# Power.net
KiCad netlist of a schematic drawn in Altium Designer
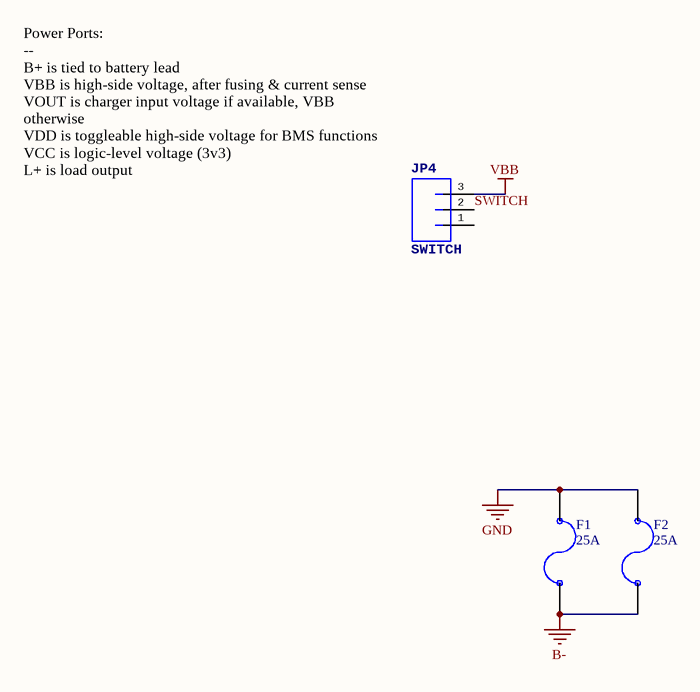
[diagram p0: Power.SchDoc]

(export (version "E")
  (design (tool "Eeschema 10.0.6"))
  (components
    (comp (ref "F1")
      (value "25A")
      (footprint "1206_FUSE")
      (description "Fuse")
      (libsource (lib "Components") (part "FUSE 1206"))
    )
    (comp (ref "F2")
      (value "25A")
      (footprint "1206_FUSE")
      (description "Fuse")
      (libsource (lib "Components") (part "FUSE 1206"))
    )
    (comp (ref "JP4")
      (value "SWITCH")
      (footprint "JST-3-PTH-VERT")
      (libsource (lib "Components") (part "JST_3"))
    )
  )
  (nets
    (net (code "1") (name "/SWITCH") (class "Default")
      (node (ref "JP4") (pin "2") (pinfunction "2_2") (pintype "passive"))
    )
    (net (code "2") (name "B-") (class "Default")
      (node (ref "F1") (pin "2") (pinfunction "2_2") (pintype "passive"))
      (node (ref "F2") (pin "2") (pinfunction "2_2") (pintype "passive"))
    )
    (net (code "3") (name "GND") (class "Default")
      (node (ref "F1") (pin "1") (pinfunction "1_1") (pintype "passive"))
      (node (ref "F2") (pin "1") (pinfunction "1_1") (pintype "passive"))
    )
    (net (code "4") (name "VBB") (class "Default")
      (node (ref "JP4") (pin "3") (pinfunction "3_3") (pintype "passive"))
    )
    (net (code "5") (name "unconnected-(JP4-Pad1)") (class "Default")
      (node (ref "JP4") (pin "1") (pinfunction "1_1") (pintype "passive"))
    )
  )
)
